# 3-bit-counter.net
KiCad netlist of a schematic drawn in EAGLE
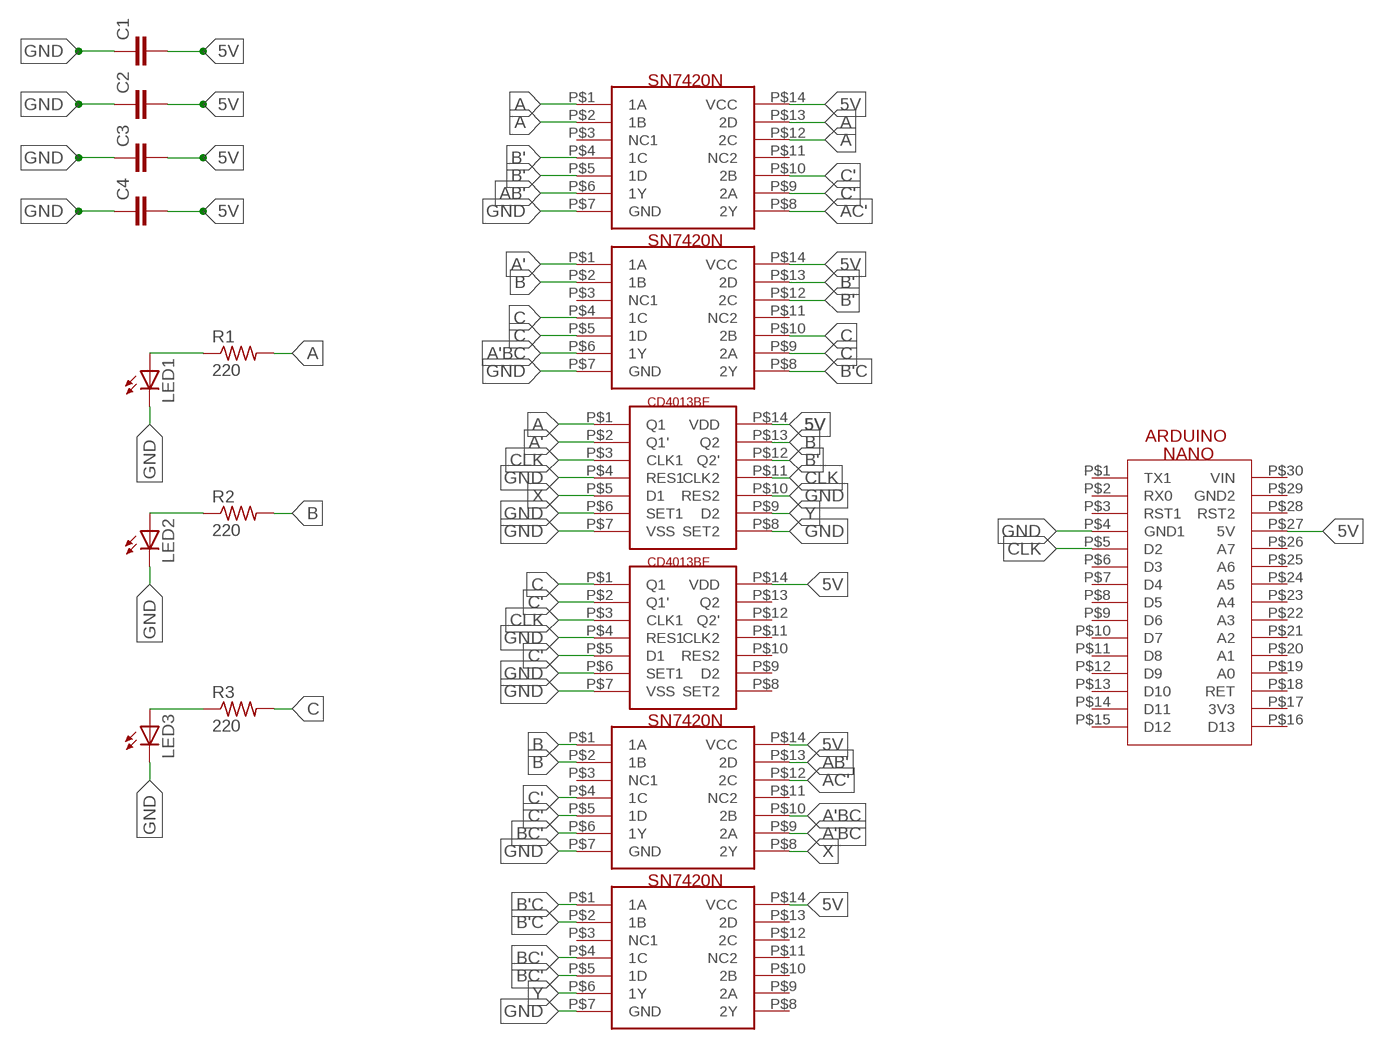
[diagram p0: schematic, sheet 1]

(export (version "E")
  (design (tool "Eeschema 10.0.6"))
  (components
    (comp (ref "C1")
      (value "C2,5-3")
      (footprint "eagle-import:C2.5-3")
      (libsource (lib "eagle-import") (part "C2,5-3"))
    )
    (comp (ref "C2")
      (value "C2,5-3")
      (footprint "eagle-import:C2.5-3")
      (libsource (lib "eagle-import") (part "C2,5-3"))
    )
    (comp (ref "C3")
      (value "C2,5-3")
      (footprint "eagle-import:C2.5-3")
      (libsource (lib "eagle-import") (part "C2,5-3"))
    )
    (comp (ref "C4")
      (value "C2,5-3")
      (footprint "eagle-import:C2.5-3")
      (libsource (lib "eagle-import") (part "C2,5-3"))
    )
    (comp (ref "DFF1")
      (value "MC_DFFDIP14")
      (footprint "eagle-import:DIP14")
      (libsource (lib "eagle-import") (part "MC_DFFDIP14"))
    )
    (comp (ref "DFF2")
      (value "MC_DFFDIP14")
      (footprint "eagle-import:DIP14")
      (libsource (lib "eagle-import") (part "MC_DFFDIP14"))
    )
    (comp (ref "LED1")
      (value "LED5MM")
      (footprint "eagle-import:LED5MM")
      (libsource (lib "eagle-import") (part "LED5MM"))
    )
    (comp (ref "LED2")
      (value "LED5MM")
      (footprint "eagle-import:LED5MM")
      (libsource (lib "eagle-import") (part "LED5MM"))
    )
    (comp (ref "LED3")
      (value "LED5MM")
      (footprint "eagle-import:LED5MM")
      (libsource (lib "eagle-import") (part "LED5MM"))
    )
    (comp (ref "NAND1")
      (value "MC_NANDDIP14")
      (footprint "eagle-import:DIP14")
      (libsource (lib "eagle-import") (part "MC_NANDDIP14"))
    )
    (comp (ref "NAND2")
      (value "MC_NANDDIP14")
      (footprint "eagle-import:DIP14")
      (libsource (lib "eagle-import") (part "MC_NANDDIP14"))
    )
    (comp (ref "NAND3")
      (value "MC_NANDDIP14")
      (footprint "eagle-import:DIP14")
      (libsource (lib "eagle-import") (part "MC_NANDDIP14"))
    )
    (comp (ref "NAND4")
      (value "MC_NANDDIP14")
      (footprint "eagle-import:DIP14")
      (libsource (lib "eagle-import") (part "MC_NANDDIP14"))
    )
    (comp (ref "R1")
      (value "220")
      (footprint "eagle-import:0204_7")
      (libsource (lib "eagle-import") (part "R-US_0204/7"))
    )
    (comp (ref "R2")
      (value "220")
      (footprint "eagle-import:0204_7")
      (libsource (lib "eagle-import") (part "R-US_0204/7"))
    )
    (comp (ref "R3")
      (value "220")
      (footprint "eagle-import:0204_7")
      (libsource (lib "eagle-import") (part "R-US_0204/7"))
    )
    (comp (ref "U$7")
      (value "MC_NANO")
      (footprint "eagle-import:MC_NANO")
      (libsource (lib "eagle-import") (part "MC_NANO"))
    )
  )
  (nets
    (net (code "1") (name "5V") (class "Default")
      (node (ref "C1") (pin "2") (pinfunction "2_2") (pintype "passive"))
      (node (ref "C2") (pin "2") (pinfunction "2_2") (pintype "passive"))
      (node (ref "C3") (pin "2") (pinfunction "2_2") (pintype "passive"))
      (node (ref "C4") (pin "2") (pinfunction "2_2") (pintype "passive"))
      (node (ref "DFF1") (pin "P$14") (pinfunction "VDD_P$14") (pintype "bidirectional"))
      (node (ref "DFF2") (pin "P$14") (pinfunction "VDD_P$14") (pintype "bidirectional"))
      (node (ref "NAND1") (pin "P$14") (pinfunction "VCC_P$14") (pintype "bidirectional"))
      (node (ref "NAND2") (pin "P$14") (pinfunction "VCC_P$14") (pintype "bidirectional"))
      (node (ref "NAND3") (pin "P$14") (pinfunction "VCC_P$14") (pintype "bidirectional"))
      (node (ref "NAND4") (pin "P$14") (pinfunction "VCC_P$14") (pintype "bidirectional"))
      (node (ref "U$7") (pin "P$27") (pinfunction "5V_P$27") (pintype "bidirectional"))
    )
    (net (code "2") (name "A") (class "Default")
      (node (ref "DFF1") (pin "P$1") (pinfunction "Q1_P$1") (pintype "bidirectional"))
      (node (ref "NAND1") (pin "P$1") (pinfunction "1A_P$1") (pintype "bidirectional"))
      (node (ref "NAND1") (pin "P$12") (pinfunction "2C_P$12") (pintype "bidirectional"))
      (node (ref "NAND1") (pin "P$13") (pinfunction "2D_P$13") (pintype "bidirectional"))
      (node (ref "NAND1") (pin "P$2") (pinfunction "1B_P$2") (pintype "bidirectional"))
      (node (ref "R1") (pin "2") (pinfunction "2_2") (pintype "passive"))
    )
    (net (code "3") (name "A'") (class "Default")
      (node (ref "DFF1") (pin "P$2") (pinfunction "Q1'_P$2") (pintype "bidirectional"))
      (node (ref "NAND2") (pin "P$1") (pinfunction "1A_P$1") (pintype "bidirectional"))
    )
    (net (code "4") (name "A'BC") (class "Default")
      (node (ref "NAND2") (pin "P$6") (pinfunction "1Y_P$6") (pintype "bidirectional"))
      (node (ref "NAND3") (pin "P$10") (pinfunction "2B_P$10") (pintype "bidirectional"))
      (node (ref "NAND3") (pin "P$9") (pinfunction "2A_P$9") (pintype "bidirectional"))
    )
    (net (code "5") (name "AB'") (class "Default")
      (node (ref "NAND1") (pin "P$6") (pinfunction "1Y_P$6") (pintype "bidirectional"))
      (node (ref "NAND3") (pin "P$13") (pinfunction "2D_P$13") (pintype "bidirectional"))
    )
    (net (code "6") (name "AC'") (class "Default")
      (node (ref "NAND1") (pin "P$8") (pinfunction "2Y_P$8") (pintype "bidirectional"))
      (node (ref "NAND3") (pin "P$12") (pinfunction "2C_P$12") (pintype "bidirectional"))
    )
    (net (code "7") (name "B") (class "Default")
      (node (ref "DFF1") (pin "P$13") (pinfunction "Q2_P$13") (pintype "bidirectional"))
      (node (ref "NAND2") (pin "P$2") (pinfunction "1B_P$2") (pintype "bidirectional"))
      (node (ref "NAND3") (pin "P$1") (pinfunction "1A_P$1") (pintype "bidirectional"))
      (node (ref "NAND3") (pin "P$2") (pinfunction "1B_P$2") (pintype "bidirectional"))
      (node (ref "R2") (pin "2") (pinfunction "2_2") (pintype "passive"))
    )
    (net (code "8") (name "B'") (class "Default")
      (node (ref "DFF1") (pin "P$12") (pinfunction "Q2'_P$12") (pintype "bidirectional"))
      (node (ref "NAND1") (pin "P$4") (pinfunction "1C_P$4") (pintype "bidirectional"))
      (node (ref "NAND1") (pin "P$5") (pinfunction "1D_P$5") (pintype "bidirectional"))
      (node (ref "NAND2") (pin "P$12") (pinfunction "2C_P$12") (pintype "bidirectional"))
      (node (ref "NAND2") (pin "P$13") (pinfunction "2D_P$13") (pintype "bidirectional"))
    )
    (net (code "9") (name "B'C") (class "Default")
      (node (ref "NAND2") (pin "P$8") (pinfunction "2Y_P$8") (pintype "bidirectional"))
      (node (ref "NAND4") (pin "P$1") (pinfunction "1A_P$1") (pintype "bidirectional"))
      (node (ref "NAND4") (pin "P$2") (pinfunction "1B_P$2") (pintype "bidirectional"))
    )
    (net (code "10") (name "BC'") (class "Default")
      (node (ref "NAND3") (pin "P$6") (pinfunction "1Y_P$6") (pintype "bidirectional"))
      (node (ref "NAND4") (pin "P$4") (pinfunction "1C_P$4") (pintype "bidirectional"))
      (node (ref "NAND4") (pin "P$5") (pinfunction "1D_P$5") (pintype "bidirectional"))
    )
    (net (code "11") (name "C") (class "Default")
      (node (ref "DFF2") (pin "P$1") (pinfunction "Q1_P$1") (pintype "bidirectional"))
      (node (ref "NAND2") (pin "P$10") (pinfunction "2B_P$10") (pintype "bidirectional"))
      (node (ref "NAND2") (pin "P$4") (pinfunction "1C_P$4") (pintype "bidirectional"))
      (node (ref "NAND2") (pin "P$5") (pinfunction "1D_P$5") (pintype "bidirectional"))
      (node (ref "NAND2") (pin "P$9") (pinfunction "2A_P$9") (pintype "bidirectional"))
      (node (ref "R3") (pin "2") (pinfunction "2_2") (pintype "passive"))
    )
    (net (code "12") (name "C'") (class "Default")
      (node (ref "DFF2") (pin "P$2") (pinfunction "Q1'_P$2") (pintype "bidirectional"))
      (node (ref "DFF2") (pin "P$5") (pinfunction "D1_P$5") (pintype "bidirectional"))
      (node (ref "NAND1") (pin "P$10") (pinfunction "2B_P$10") (pintype "bidirectional"))
      (node (ref "NAND1") (pin "P$9") (pinfunction "2A_P$9") (pintype "bidirectional"))
      (node (ref "NAND3") (pin "P$4") (pinfunction "1C_P$4") (pintype "bidirectional"))
      (node (ref "NAND3") (pin "P$5") (pinfunction "1D_P$5") (pintype "bidirectional"))
    )
    (net (code "13") (name "CLK") (class "Default")
      (node (ref "DFF1") (pin "P$11") (pinfunction "CLK2_P$11") (pintype "bidirectional"))
      (node (ref "DFF1") (pin "P$3") (pinfunction "CLK1_P$3") (pintype "bidirectional"))
      (node (ref "DFF2") (pin "P$3") (pinfunction "CLK1_P$3") (pintype "bidirectional"))
      (node (ref "U$7") (pin "P$5") (pinfunction "D2_P$5") (pintype "bidirectional"))
    )
    (net (code "14") (name "GND") (class "Default")
      (node (ref "C1") (pin "1") (pinfunction "1_1") (pintype "passive"))
      (node (ref "C2") (pin "1") (pinfunction "1_1") (pintype "passive"))
      (node (ref "C3") (pin "1") (pinfunction "1_1") (pintype "passive"))
      (node (ref "C4") (pin "1") (pinfunction "1_1") (pintype "passive"))
      (node (ref "DFF1") (pin "P$10") (pinfunction "RES2_P$10") (pintype "bidirectional"))
      (node (ref "DFF1") (pin "P$4") (pinfunction "RES1_P$4") (pintype "bidirectional"))
      (node (ref "DFF1") (pin "P$6") (pinfunction "SET1_P$6") (pintype "bidirectional"))
      (node (ref "DFF1") (pin "P$7") (pinfunction "VSS_P$7") (pintype "bidirectional"))
      (node (ref "DFF1") (pin "P$8") (pinfunction "SET2_P$8") (pintype "bidirectional"))
      (node (ref "DFF2") (pin "P$4") (pinfunction "RES1_P$4") (pintype "bidirectional"))
      (node (ref "DFF2") (pin "P$6") (pinfunction "SET1_P$6") (pintype "bidirectional"))
      (node (ref "DFF2") (pin "P$7") (pinfunction "VSS_P$7") (pintype "bidirectional"))
      (node (ref "LED1") (pin "K") (pinfunction "C_K") (pintype "passive"))
      (node (ref "LED2") (pin "K") (pinfunction "C_K") (pintype "passive"))
      (node (ref "LED3") (pin "K") (pinfunction "C_K") (pintype "passive"))
      (node (ref "NAND1") (pin "P$7") (pinfunction "GND_P$7") (pintype "bidirectional"))
      (node (ref "NAND2") (pin "P$7") (pinfunction "GND_P$7") (pintype "bidirectional"))
      (node (ref "NAND3") (pin "P$7") (pinfunction "GND_P$7") (pintype "bidirectional"))
      (node (ref "NAND4") (pin "P$7") (pinfunction "GND_P$7") (pintype "bidirectional"))
      (node (ref "U$7") (pin "P$4") (pinfunction "GND1_P$4") (pintype "bidirectional"))
    )
    (net (code "15") (name "Net-(LED1-PadA)") (class "Default")
      (node (ref "LED1") (pin "A") (pinfunction "A_A") (pintype "passive"))
      (node (ref "R1") (pin "1") (pinfunction "1_1") (pintype "passive"))
    )
    (net (code "16") (name "Net-(LED2-PadA)") (class "Default")
      (node (ref "LED2") (pin "A") (pinfunction "A_A") (pintype "passive"))
      (node (ref "R2") (pin "1") (pinfunction "1_1") (pintype "passive"))
    )
    (net (code "17") (name "Net-(LED3-PadA)") (class "Default")
      (node (ref "LED3") (pin "A") (pinfunction "A_A") (pintype "passive"))
      (node (ref "R3") (pin "1") (pinfunction "1_1") (pintype "passive"))
    )
    (net (code "18") (name "X") (class "Default")
      (node (ref "DFF1") (pin "P$5") (pinfunction "D1_P$5") (pintype "bidirectional"))
      (node (ref "NAND3") (pin "P$8") (pinfunction "2Y_P$8") (pintype "bidirectional"))
    )
    (net (code "19") (name "Y") (class "Default")
      (node (ref "DFF1") (pin "P$9") (pinfunction "D2_P$9") (pintype "bidirectional"))
      (node (ref "NAND4") (pin "P$6") (pinfunction "1Y_P$6") (pintype "bidirectional"))
    )
    (net (code "20") (name "unconnected-(DFF2-CLK2-PadP$11)") (class "Default")
      (node (ref "DFF2") (pin "P$11") (pinfunction "CLK2_P$11") (pintype "bidirectional"))
    )
    (net (code "21") (name "unconnected-(DFF2-D2-PadP$9)") (class "Default")
      (node (ref "DFF2") (pin "P$9") (pinfunction "D2_P$9") (pintype "bidirectional"))
    )
    (net (code "22") (name "unconnected-(DFF2-Q2'-PadP$12)") (class "Default")
      (node (ref "DFF2") (pin "P$12") (pinfunction "Q2'_P$12") (pintype "bidirectional"))
    )
    (net (code "23") (name "unconnected-(DFF2-Q2-PadP$13)") (class "Default")
      (node (ref "DFF2") (pin "P$13") (pinfunction "Q2_P$13") (pintype "bidirectional"))
    )
    (net (code "24") (name "unconnected-(DFF2-RES2-PadP$10)") (class "Default")
      (node (ref "DFF2") (pin "P$10") (pinfunction "RES2_P$10") (pintype "bidirectional"))
    )
    (net (code "25") (name "unconnected-(DFF2-SET2-PadP$8)") (class "Default")
      (node (ref "DFF2") (pin "P$8") (pinfunction "SET2_P$8") (pintype "bidirectional"))
    )
    (net (code "26") (name "unconnected-(NAND1-NC1-PadP$3)") (class "Default")
      (node (ref "NAND1") (pin "P$3") (pinfunction "NC1_P$3") (pintype "bidirectional"))
    )
    (net (code "27") (name "unconnected-(NAND1-NC2-PadP$11)") (class "Default")
      (node (ref "NAND1") (pin "P$11") (pinfunction "NC2_P$11") (pintype "bidirectional"))
    )
    (net (code "28") (name "unconnected-(NAND2-NC1-PadP$3)") (class "Default")
      (node (ref "NAND2") (pin "P$3") (pinfunction "NC1_P$3") (pintype "bidirectional"))
    )
    (net (code "29") (name "unconnected-(NAND2-NC2-PadP$11)") (class "Default")
      (node (ref "NAND2") (pin "P$11") (pinfunction "NC2_P$11") (pintype "bidirectional"))
    )
    (net (code "30") (name "unconnected-(NAND3-NC1-PadP$3)") (class "Default")
      (node (ref "NAND3") (pin "P$3") (pinfunction "NC1_P$3") (pintype "bidirectional"))
    )
    (net (code "31") (name "unconnected-(NAND3-NC2-PadP$11)") (class "Default")
      (node (ref "NAND3") (pin "P$11") (pinfunction "NC2_P$11") (pintype "bidirectional"))
    )
    (net (code "32") (name "unconnected-(NAND4-2A-PadP$9)") (class "Default")
      (node (ref "NAND4") (pin "P$9") (pinfunction "2A_P$9") (pintype "bidirectional"))
    )
    (net (code "33") (name "unconnected-(NAND4-2B-PadP$10)") (class "Default")
      (node (ref "NAND4") (pin "P$10") (pinfunction "2B_P$10") (pintype "bidirectional"))
    )
    (net (code "34") (name "unconnected-(NAND4-2C-PadP$12)") (class "Default")
      (node (ref "NAND4") (pin "P$12") (pinfunction "2C_P$12") (pintype "bidirectional"))
    )
    (net (code "35") (name "unconnected-(NAND4-2D-PadP$13)") (class "Default")
      (node (ref "NAND4") (pin "P$13") (pinfunction "2D_P$13") (pintype "bidirectional"))
    )
    (net (code "36") (name "unconnected-(NAND4-2Y-PadP$8)") (class "Default")
      (node (ref "NAND4") (pin "P$8") (pinfunction "2Y_P$8") (pintype "bidirectional"))
    )
    (net (code "37") (name "unconnected-(NAND4-NC1-PadP$3)") (class "Default")
      (node (ref "NAND4") (pin "P$3") (pinfunction "NC1_P$3") (pintype "bidirectional"))
    )
    (net (code "38") (name "unconnected-(NAND4-NC2-PadP$11)") (class "Default")
      (node (ref "NAND4") (pin "P$11") (pinfunction "NC2_P$11") (pintype "bidirectional"))
    )
    (net (code "39") (name "unconnected-(U$7-3V3-PadP$17)") (class "Default")
      (node (ref "U$7") (pin "P$17") (pinfunction "3V3_P$17") (pintype "bidirectional"))
    )
    (net (code "40") (name "unconnected-(U$7-A0-PadP$19)") (class "Default")
      (node (ref "U$7") (pin "P$19") (pinfunction "A0_P$19") (pintype "bidirectional"))
    )
    (net (code "41") (name "unconnected-(U$7-A1-PadP$20)") (class "Default")
      (node (ref "U$7") (pin "P$20") (pinfunction "A1_P$20") (pintype "bidirectional"))
    )
    (net (code "42") (name "unconnected-(U$7-A2-PadP$21)") (class "Default")
      (node (ref "U$7") (pin "P$21") (pinfunction "A2_P$21") (pintype "bidirectional"))
    )
    (net (code "43") (name "unconnected-(U$7-A3-PadP$22)") (class "Default")
      (node (ref "U$7") (pin "P$22") (pinfunction "A3_P$22") (pintype "bidirectional"))
    )
    (net (code "44") (name "unconnected-(U$7-A4-PadP$23)") (class "Default")
      (node (ref "U$7") (pin "P$23") (pinfunction "A4_P$23") (pintype "bidirectional"))
    )
    (net (code "45") (name "unconnected-(U$7-A5-PadP$24)") (class "Default")
      (node (ref "U$7") (pin "P$24") (pinfunction "A5_P$24") (pintype "bidirectional"))
    )
    (net (code "46") (name "unconnected-(U$7-A6-PadP$25)") (class "Default")
      (node (ref "U$7") (pin "P$25") (pinfunction "A6_P$25") (pintype "bidirectional"))
    )
    (net (code "47") (name "unconnected-(U$7-A7-PadP$26)") (class "Default")
      (node (ref "U$7") (pin "P$26") (pinfunction "A7_P$26") (pintype "bidirectional"))
    )
    (net (code "48") (name "unconnected-(U$7-D3-PadP$6)") (class "Default")
      (node (ref "U$7") (pin "P$6") (pinfunction "D3_P$6") (pintype "bidirectional"))
    )
    (net (code "49") (name "unconnected-(U$7-D4-PadP$7)") (class "Default")
      (node (ref "U$7") (pin "P$7") (pinfunction "D4_P$7") (pintype "bidirectional"))
    )
    (net (code "50") (name "unconnected-(U$7-D5-PadP$8)") (class "Default")
      (node (ref "U$7") (pin "P$8") (pinfunction "D5_P$8") (pintype "bidirectional"))
    )
    (net (code "51") (name "unconnected-(U$7-D6-PadP$9)") (class "Default")
      (node (ref "U$7") (pin "P$9") (pinfunction "D6_P$9") (pintype "bidirectional"))
    )
    (net (code "52") (name "unconnected-(U$7-D7-PadP$10)") (class "Default")
      (node (ref "U$7") (pin "P$10") (pinfunction "D7_P$10") (pintype "bidirectional"))
    )
    (net (code "53") (name "unconnected-(U$7-D8-PadP$11)") (class "Default")
      (node (ref "U$7") (pin "P$11") (pinfunction "D8_P$11") (pintype "bidirectional"))
    )
    (net (code "54") (name "unconnected-(U$7-D9-PadP$12)") (class "Default")
      (node (ref "U$7") (pin "P$12") (pinfunction "D9_P$12") (pintype "bidirectional"))
    )
    (net (code "55") (name "unconnected-(U$7-D10-PadP$13)") (class "Default")
      (node (ref "U$7") (pin "P$13") (pinfunction "D10_P$13") (pintype "bidirectional"))
    )
    (net (code "56") (name "unconnected-(U$7-D11-PadP$14)") (class "Default")
      (node (ref "U$7") (pin "P$14") (pinfunction "D11_P$14") (pintype "bidirectional"))
    )
    (net (code "57") (name "unconnected-(U$7-D12-PadP$15)") (class "Default")
      (node (ref "U$7") (pin "P$15") (pinfunction "D12_P$15") (pintype "bidirectional"))
    )
    (net (code "58") (name "unconnected-(U$7-D13-PadP$16)") (class "Default")
      (node (ref "U$7") (pin "P$16") (pinfunction "D13_P$16") (pintype "bidirectional"))
    )
    (net (code "59") (name "unconnected-(U$7-GND2-PadP$29)") (class "Default")
      (node (ref "U$7") (pin "P$29") (pinfunction "GND2_P$29") (pintype "bidirectional"))
    )
    (net (code "60") (name "unconnected-(U$7-RET-PadP$18)") (class "Default")
      (node (ref "U$7") (pin "P$18") (pinfunction "RET_P$18") (pintype "bidirectional"))
    )
    (net (code "61") (name "unconnected-(U$7-RST1-PadP$3)") (class "Default")
      (node (ref "U$7") (pin "P$3") (pinfunction "RST1_P$3") (pintype "bidirectional"))
    )
    (net (code "62") (name "unconnected-(U$7-RST2-PadP$28)") (class "Default")
      (node (ref "U$7") (pin "P$28") (pinfunction "RST2_P$28") (pintype "bidirectional"))
    )
    (net (code "63") (name "unconnected-(U$7-RX0-PadP$2)") (class "Default")
      (node (ref "U$7") (pin "P$2") (pinfunction "RX0_P$2") (pintype "bidirectional"))
    )
    (net (code "64") (name "unconnected-(U$7-TX1-PadP$1)") (class "Default")
      (node (ref "U$7") (pin "P$1") (pinfunction "TX1_P$1") (pintype "bidirectional"))
    )
    (net (code "65") (name "unconnected-(U$7-VIN-PadP$30)") (class "Default")
      (node (ref "U$7") (pin "P$30") (pinfunction "VIN_P$30") (pintype "bidirectional"))
    )
  )
)
